# smd.net
KiCad netlist of a schematic drawn in EAGLE
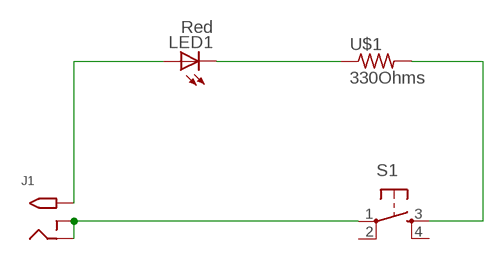
[diagram p0: schematic, sheet 1]

(export (version "E")
  (design (tool "Eeschema 10.0.6"))
  (components
    (comp (ref "J1")
      (value "2.1MMJACKTHM")
      (footprint "eagle-import:PJ-102A")
      (libsource (lib "eagle-import") (part "2.1MMJACKTHM"))
    )
    (comp (ref "LED1")
      (value "Red")
      (footprint "eagle-import:LED5MM")
      (libsource (lib "eagle-import") (part "LED5MM"))
    )
    (comp (ref "S1")
      (value "BUTTON-TACTILESURFACE_MOUNT")
      (footprint "eagle-import:1301.9315-LSH")
      (libsource (lib "eagle-import") (part "BUTTON-TACTILESURFACE_MOUNT"))
    )
    (comp (ref "U$1")
      (value "330Ohms")
      (footprint "eagle-import:RESAD1160W55L680D260_HS")
      (libsource (lib "eagle-import") (part "RESISTORTH-1/4W-CARBON"))
    )
  )
  (nets
    (net (code "1") (name "Net-(J1-PadTIP)") (class "Default")
      (node (ref "J1") (pin "TIP") (pinfunction "TIP_TIP") (pintype "bidirectional"))
      (node (ref "LED1") (pin "A") (pinfunction "A_A") (pintype "passive"))
    )
    (net (code "2") (name "Net-(LED1-C)") (class "Default")
      (node (ref "LED1") (pin "K") (pinfunction "C_K") (pintype "passive"))
      (node (ref "U$1") (pin "1") (pinfunction "1_1") (pintype "passive"))
    )
    (net (code "3") (name "Net-(S1-P)") (class "Default")
      (node (ref "J1") (pin "RING") (pinfunction "RING_RING") (pintype "bidirectional"))
      (node (ref "J1") (pin "RING_SW") (pinfunction "RING_SW_RING_SW") (pintype "bidirectional"))
      (node (ref "S1") (pin "1") (pinfunction "P_1") (pintype "passive"))
    )
    (net (code "4") (name "Net-(S1-S)") (class "Default")
      (node (ref "S1") (pin "3") (pinfunction "S_3") (pintype "passive"))
      (node (ref "U$1") (pin "2") (pinfunction "2_2") (pintype "passive"))
    )
    (net (code "5") (name "unconnected-(S1-P1-Pad2)") (class "Default")
      (node (ref "S1") (pin "2") (pinfunction "P1_2") (pintype "passive"))
    )
    (net (code "6") (name "unconnected-(S1-S1-Pad4)") (class "Default")
      (node (ref "S1") (pin "4") (pinfunction "S1_4") (pintype "passive"))
    )
  )
)
